# cpu.net
KiCad netlist of a schematic drawn in Altium Designer
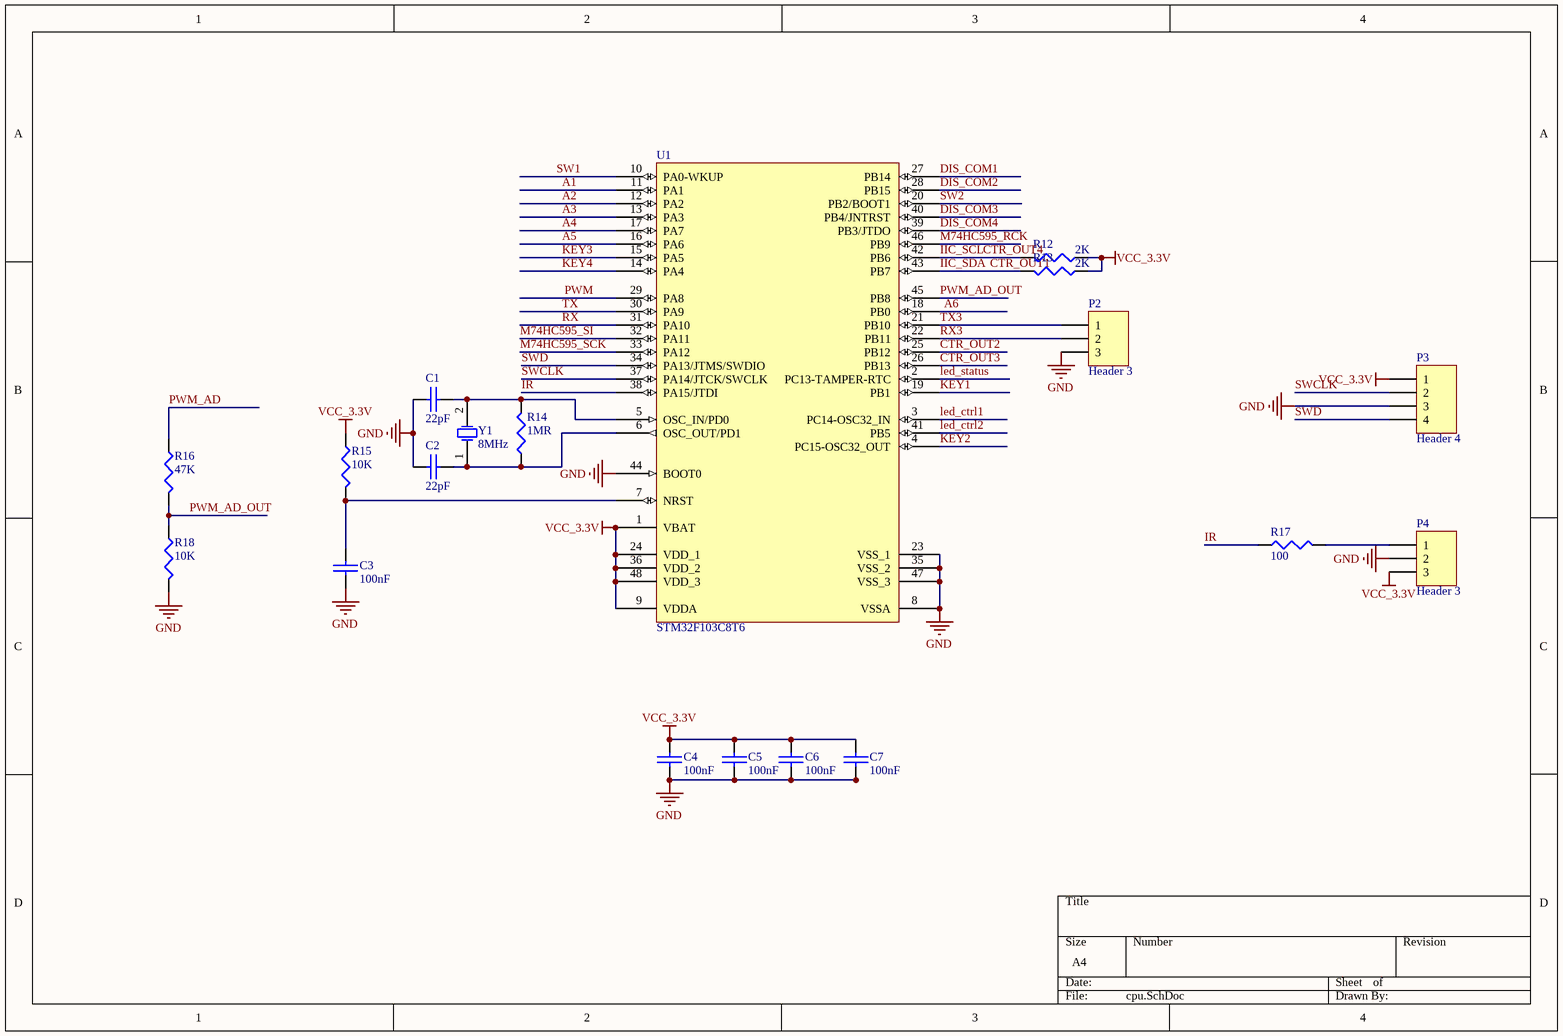
[diagram p0: cpu.SchDoc]

(export (version "E")
  (design (tool "Eeschema 10.0.6"))
  (components
    (comp (ref "C1")
      (value "22pF")
      (footprint "0805c")
      (description "Capacitor")
      (libsource (lib "SM") (part "CAP"))
    )
    (comp (ref "C2")
      (value "22pF")
      (footprint "0805c")
      (description "Capacitor")
      (libsource (lib "SM") (part "CAP"))
    )
    (comp (ref "C3")
      (value "100nF")
      (footprint "0805c")
      (description "Capacitor")
      (libsource (lib "SM") (part "CAP"))
    )
    (comp (ref "C4")
      (value "100nF")
      (footprint "0805c")
      (description "Capacitor")
      (libsource (lib "SM") (part "CAP"))
    )
    (comp (ref "C5")
      (value "100nF")
      (footprint "0805c")
      (description "Capacitor")
      (libsource (lib "SM") (part "CAP"))
    )
    (comp (ref "C6")
      (value "100nF")
      (footprint "0805c")
      (description "Capacitor")
      (libsource (lib "SM") (part "CAP"))
    )
    (comp (ref "C7")
      (value "100nF")
      (footprint "0805c")
      (description "Capacitor")
      (libsource (lib "SM") (part "CAP"))
    )
    (comp (ref "P2")
      (value "Header 3")
      (footprint "HDR1X3")
      (description "Header, 3-Pin")
      (fields (field (name "PUBLISHER") "Altium Limited"))
      (libsource (lib "Miscellaneous Connectors") (part "Header 3"))
    )
    (comp (ref "P3")
      (value "Header 4")
      (footprint "HDR1X4")
      (description "Header, 4-Pin")
      (fields (field (name "PUBLISHER") "Altium Limited"))
      (libsource (lib "Miscellaneous Connectors") (part "Header 4"))
    )
    (comp (ref "P4")
      (value "Header 3")
      (footprint "HDR1X3")
      (description "Header, 3-Pin")
      (fields (field (name "PUBLISHER") "Altium Limited"))
      (libsource (lib "Miscellaneous Connectors") (part "Header 3"))
    )
    (comp (ref "R12")
      (value "2K")
      (footprint "0805R")
      (description "Resistor")
      (fields (field (name "PUBLISHER") "Altium Limited"))
      (libsource (lib "SM") (part "Res3"))
    )
    (comp (ref "R13")
      (value "2K")
      (footprint "0805R")
      (description "Resistor")
      (fields (field (name "PUBLISHER") "Altium Limited"))
      (libsource (lib "SM") (part "Res3"))
    )
    (comp (ref "R14")
      (value "1MR")
      (footprint "0805R")
      (description "Resistor")
      (fields (field (name "PUBLISHER") "Altium Limited"))
      (libsource (lib "SM") (part "Res3"))
    )
    (comp (ref "R15")
      (value "10K")
      (footprint "0805R")
      (description "Resistor")
      (fields (field (name "PUBLISHER") "Altium Limited"))
      (libsource (lib "SM") (part "Res3"))
    )
    (comp (ref "R16")
      (value "47K")
      (footprint "0805R")
      (description "Resistor")
      (fields (field (name "PUBLISHER") "Altium Limited"))
      (libsource (lib "SM") (part "Res3"))
    )
    (comp (ref "R17")
      (value "100")
      (footprint "0805R")
      (description "Resistor")
      (fields (field (name "PUBLISHER") "Altium Limited"))
      (libsource (lib "SM") (part "Res3"))
    )
    (comp (ref "R18")
      (value "10K")
      (footprint "0805R")
      (description "Resistor")
      (fields (field (name "PUBLISHER") "Altium Limited"))
      (libsource (lib "SM") (part "Res3"))
    )
    (comp (ref "U1")
      (value "STM32F103C8T6")
      (footprint "TQFP-48")
      (description "STM32 ARM-based 32-bit MCU with 64 Kbytes Flash, 48-pin LQFP, Industrial Temperature")
      (fields (field (name "PUBLISHER") "Altium Limited"))
      (libsource (lib "ST Microcontroller 32-Bit STM32") (part "STM32F103C8T6"))
    )
    (comp (ref "Y1")
      (value "8MHz")
      (footprint "SMT5032")
      (description "Crystal Oscillator")
      (fields (field (name "PUBLISHER") "Altium Limited"))
      (libsource (lib "Miscellaneous Devices") (part "XTAL"))
    )
  )
  (nets
    (net (code "1") (name "/A1") (class "Default")
      (node (ref "U1") (pin "11") (pinfunction "PA1_11") (pintype "bidirectional"))
    )
    (net (code "2") (name "/A2") (class "Default")
      (node (ref "U1") (pin "12") (pinfunction "PA2_12") (pintype "bidirectional"))
    )
    (net (code "3") (name "/A3") (class "Default")
      (node (ref "U1") (pin "13") (pinfunction "PA3_13") (pintype "bidirectional"))
    )
    (net (code "4") (name "/A4") (class "Default")
      (node (ref "U1") (pin "17") (pinfunction "PA7_17") (pintype "bidirectional"))
    )
    (net (code "5") (name "/A5") (class "Default")
      (node (ref "U1") (pin "16") (pinfunction "PA6_16") (pintype "bidirectional"))
    )
    (net (code "6") (name "/A6") (class "Default")
      (node (ref "U1") (pin "18") (pinfunction "PB0_18") (pintype "bidirectional"))
    )
    (net (code "7") (name "/CTR_OUT1") (class "Default")
      (node (ref "R13") (pin "2") (pinfunction "2_2") (pintype "passive"))
      (node (ref "U1") (pin "43") (pinfunction "PB7_43") (pintype "bidirectional"))
    )
    (net (code "8") (name "/CTR_OUT2") (class "Default")
      (node (ref "U1") (pin "25") (pinfunction "PB12_25") (pintype "bidirectional"))
    )
    (net (code "9") (name "/CTR_OUT3") (class "Default")
      (node (ref "U1") (pin "26") (pinfunction "PB13_26") (pintype "bidirectional"))
    )
    (net (code "10") (name "/CTR_OUT4") (class "Default")
      (node (ref "R12") (pin "2") (pinfunction "2_2") (pintype "passive"))
      (node (ref "U1") (pin "42") (pinfunction "PB6_42") (pintype "bidirectional"))
    )
    (net (code "11") (name "/DIS_COM1") (class "Default")
      (node (ref "U1") (pin "27") (pinfunction "PB14_27") (pintype "bidirectional"))
    )
    (net (code "12") (name "/DIS_COM2") (class "Default")
      (node (ref "U1") (pin "28") (pinfunction "PB15_28") (pintype "bidirectional"))
    )
    (net (code "13") (name "/DIS_COM3") (class "Default")
      (node (ref "U1") (pin "40") (pinfunction "PB4/JNTRST_40") (pintype "bidirectional"))
    )
    (net (code "14") (name "/DIS_COM4") (class "Default")
      (node (ref "U1") (pin "39") (pinfunction "PB3/JTDO_39") (pintype "bidirectional"))
    )
    (net (code "15") (name "/IR") (class "Default")
      (node (ref "R17") (pin "1") (pinfunction "1_1") (pintype "passive"))
      (node (ref "U1") (pin "38") (pinfunction "PA15/JTDI_38") (pintype "bidirectional"))
    )
    (net (code "16") (name "/KEY1") (class "Default")
      (node (ref "U1") (pin "19") (pinfunction "PB1_19") (pintype "bidirectional"))
    )
    (net (code "17") (name "/KEY2") (class "Default")
      (node (ref "U1") (pin "4") (pinfunction "PC15-OSC32_OUT_4") (pintype "bidirectional"))
    )
    (net (code "18") (name "/KEY3") (class "Default")
      (node (ref "U1") (pin "15") (pinfunction "PA5_15") (pintype "bidirectional"))
    )
    (net (code "19") (name "/KEY4") (class "Default")
      (node (ref "U1") (pin "14") (pinfunction "PA4_14") (pintype "bidirectional"))
    )
    (net (code "20") (name "/M74HC595_RCK") (class "Default")
      (node (ref "U1") (pin "46") (pinfunction "PB9_46") (pintype "bidirectional"))
    )
    (net (code "21") (name "/M74HC595_SCK") (class "Default")
      (node (ref "U1") (pin "33") (pinfunction "PA12_33") (pintype "bidirectional"))
    )
    (net (code "22") (name "/M74HC595_SI") (class "Default")
      (node (ref "U1") (pin "32") (pinfunction "PA11_32") (pintype "bidirectional"))
    )
    (net (code "23") (name "/PWM") (class "Default")
      (node (ref "U1") (pin "29") (pinfunction "PA8_29") (pintype "bidirectional"))
    )
    (net (code "24") (name "/PWM_AD") (class "Default")
      (node (ref "R16") (pin "1") (pinfunction "1_1") (pintype "passive"))
    )
    (net (code "25") (name "/PWM_AD_OUT") (class "Default")
      (node (ref "R16") (pin "2") (pinfunction "2_2") (pintype "passive"))
      (node (ref "R18") (pin "1") (pinfunction "1_1") (pintype "passive"))
      (node (ref "U1") (pin "45") (pinfunction "PB8_45") (pintype "bidirectional"))
    )
    (net (code "26") (name "/RX") (class "Default")
      (node (ref "U1") (pin "31") (pinfunction "PA10_31") (pintype "bidirectional"))
    )
    (net (code "27") (name "/RX3") (class "Default")
      (node (ref "P2") (pin "2") (pinfunction "2_2") (pintype "passive"))
      (node (ref "U1") (pin "22") (pinfunction "PB11_22") (pintype "bidirectional"))
    )
    (net (code "28") (name "/SW1") (class "Default")
      (node (ref "U1") (pin "10") (pinfunction "PA0-WKUP_10") (pintype "bidirectional"))
    )
    (net (code "29") (name "/SW2") (class "Default")
      (node (ref "U1") (pin "20") (pinfunction "PB2/BOOT1_20") (pintype "bidirectional"))
    )
    (net (code "30") (name "/SWCLK") (class "Default")
      (node (ref "P3") (pin "2") (pinfunction "2_2") (pintype "passive"))
      (node (ref "U1") (pin "37") (pinfunction "PA14/JTCK/SWCLK_37") (pintype "bidirectional"))
    )
    (net (code "31") (name "/SWD") (class "Default")
      (node (ref "P3") (pin "4") (pinfunction "4_4") (pintype "passive"))
      (node (ref "U1") (pin "34") (pinfunction "PA13/JTMS/SWDIO_34") (pintype "bidirectional"))
    )
    (net (code "32") (name "/TX") (class "Default")
      (node (ref "U1") (pin "30") (pinfunction "PA9_30") (pintype "bidirectional"))
    )
    (net (code "33") (name "/TX3") (class "Default")
      (node (ref "P2") (pin "1") (pinfunction "1_1") (pintype "passive"))
      (node (ref "U1") (pin "21") (pinfunction "PB10_21") (pintype "bidirectional"))
    )
    (net (code "34") (name "/led_ctrl1") (class "Default")
      (node (ref "U1") (pin "3") (pinfunction "PC14-OSC32_IN_3") (pintype "bidirectional"))
    )
    (net (code "35") (name "/led_ctrl2") (class "Default")
      (node (ref "U1") (pin "41") (pinfunction "PB5_41") (pintype "bidirectional"))
    )
    (net (code "36") (name "/led_status") (class "Default")
      (node (ref "U1") (pin "2") (pinfunction "PC13-TAMPER-RTC_2") (pintype "bidirectional"))
    )
    (net (code "37") (name "GND") (class "Default")
      (node (ref "C1") (pin "1") (pinfunction "1_1") (pintype "passive"))
      (node (ref "C2") (pin "1") (pinfunction "1_1") (pintype "passive"))
      (node (ref "C3") (pin "1") (pinfunction "1_1") (pintype "passive"))
      (node (ref "C4") (pin "1") (pinfunction "1_1") (pintype "passive"))
      (node (ref "C5") (pin "1") (pinfunction "1_1") (pintype "passive"))
      (node (ref "C6") (pin "1") (pinfunction "1_1") (pintype "passive"))
      (node (ref "C7") (pin "1") (pinfunction "1_1") (pintype "passive"))
      (node (ref "P2") (pin "3") (pinfunction "3_3") (pintype "passive"))
      (node (ref "P3") (pin "3") (pinfunction "3_3") (pintype "passive"))
      (node (ref "P4") (pin "2") (pinfunction "2_2") (pintype "passive"))
      (node (ref "R18") (pin "2") (pinfunction "2_2") (pintype "passive"))
      (node (ref "U1") (pin "23") (pinfunction "VSS_1_23") (pintype "power_in"))
      (node (ref "U1") (pin "35") (pinfunction "VSS_2_35") (pintype "power_in"))
      (node (ref "U1") (pin "44") (pinfunction "BOOT0_44") (pintype "input"))
      (node (ref "U1") (pin "47") (pinfunction "VSS_3_47") (pintype "power_in"))
      (node (ref "U1") (pin "8") (pinfunction "VSSA_8") (pintype "power_in"))
    )
    (net (code "38") (name "Net-(P4-Pad1)") (class "Default")
      (node (ref "P4") (pin "1") (pinfunction "1_1") (pintype "passive"))
      (node (ref "R17") (pin "2") (pinfunction "2_2") (pintype "passive"))
    )
    (net (code "39") (name "Net-(U1-NRST)") (class "Default")
      (node (ref "C3") (pin "2") (pinfunction "2_2") (pintype "passive"))
      (node (ref "R15") (pin "2") (pinfunction "2_2") (pintype "passive"))
      (node (ref "U1") (pin "7") (pinfunction "NRST_7") (pintype "bidirectional"))
    )
    (net (code "40") (name "Net-(U1-OSC_IN{slash}PD0)") (class "Default")
      (node (ref "C1") (pin "2") (pinfunction "2_2") (pintype "passive"))
      (node (ref "R14") (pin "2") (pinfunction "2_2") (pintype "passive"))
      (node (ref "U1") (pin "5") (pinfunction "OSC_IN/PD0_5") (pintype "input"))
      (node (ref "Y1") (pin "2") (pinfunction "OSC2_2") (pintype "passive"))
    )
    (net (code "41") (name "Net-(U1-OSC_OUT{slash}PD1)") (class "Default")
      (node (ref "C2") (pin "2") (pinfunction "2_2") (pintype "passive"))
      (node (ref "R14") (pin "1") (pinfunction "1_1") (pintype "passive"))
      (node (ref "U1") (pin "6") (pinfunction "OSC_OUT/PD1_6") (pintype "output"))
      (node (ref "Y1") (pin "1") (pinfunction "OSC1_1") (pintype "passive"))
    )
    (net (code "42") (name "VCC_3.3V") (class "Default")
      (node (ref "C4") (pin "2") (pinfunction "2_2") (pintype "passive"))
      (node (ref "C5") (pin "2") (pinfunction "2_2") (pintype "passive"))
      (node (ref "C6") (pin "2") (pinfunction "2_2") (pintype "passive"))
      (node (ref "C7") (pin "2") (pinfunction "2_2") (pintype "passive"))
      (node (ref "P3") (pin "1") (pinfunction "1_1") (pintype "passive"))
      (node (ref "P4") (pin "3") (pinfunction "3_3") (pintype "passive"))
      (node (ref "R12") (pin "1") (pinfunction "1_1") (pintype "passive"))
      (node (ref "R13") (pin "1") (pinfunction "1_1") (pintype "passive"))
      (node (ref "R15") (pin "1") (pinfunction "1_1") (pintype "passive"))
      (node (ref "U1") (pin "1") (pinfunction "VBAT_1") (pintype "power_in"))
      (node (ref "U1") (pin "24") (pinfunction "VDD_1_24") (pintype "power_in"))
      (node (ref "U1") (pin "36") (pinfunction "VDD_2_36") (pintype "power_in"))
      (node (ref "U1") (pin "48") (pinfunction "VDD_3_48") (pintype "power_in"))
      (node (ref "U1") (pin "9") (pinfunction "VDDA_9") (pintype "power_in"))
    )
  )
)
